# manual_stm_4.net
KiCad netlist of a schematic drawn in EAGLE
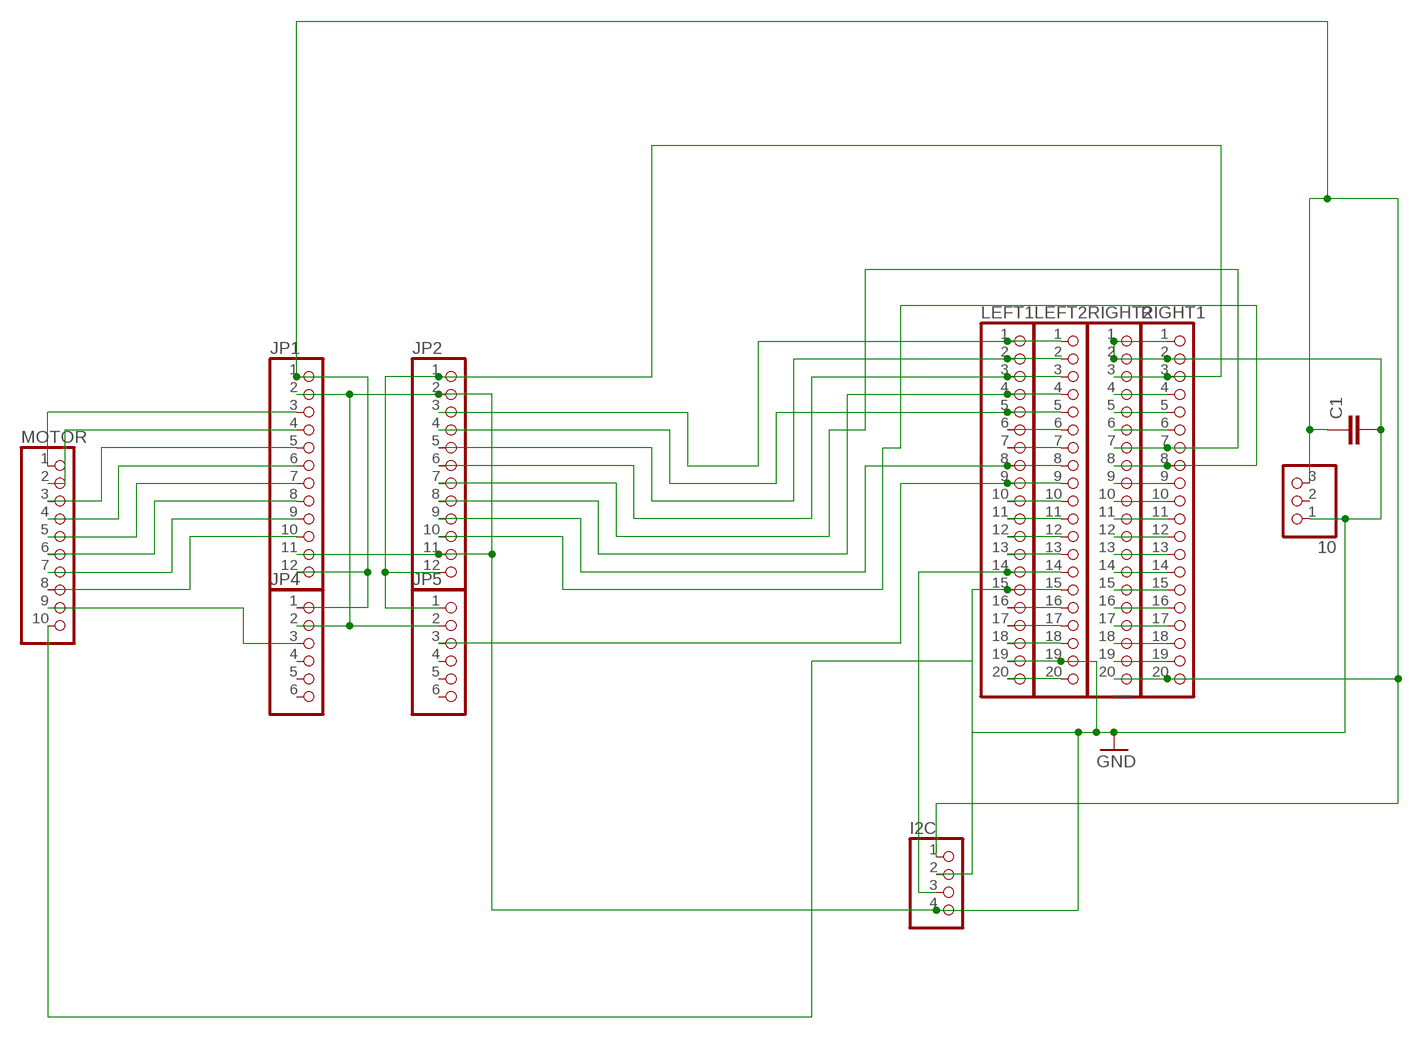
[diagram p0: schematic, sheet 1]

(export (version "E")
  (design (tool "Eeschema 10.0.6"))
  (components
    (comp (ref "10")
      (value "PINHD-1X3")
      (footprint "eagle-import:1X03")
      (libsource (lib "eagle-import") (part "PINHD-1X3"))
    )
    (comp (ref "C1")
      (value "C-EU075-032X103")
      (footprint "eagle-import:C075-032X103")
      (libsource (lib "eagle-import") (part "C-EU075-032X103"))
    )
    (comp (ref "I2C")
      (value "PINHD-1X4")
      (footprint "eagle-import:1X04")
      (libsource (lib "eagle-import") (part "PINHD-1X4"))
    )
    (comp (ref "JP1")
      (value "PINHD-1X12")
      (footprint "eagle-import:1X12")
      (libsource (lib "eagle-import") (part "PINHD-1X12"))
    )
    (comp (ref "JP2")
      (value "PINHD-1X12")
      (footprint "eagle-import:1X12")
      (libsource (lib "eagle-import") (part "PINHD-1X12"))
    )
    (comp (ref "JP4")
      (value "PINHD-1X6")
      (footprint "eagle-import:1X06")
      (libsource (lib "eagle-import") (part "PINHD-1X6"))
    )
    (comp (ref "JP5")
      (value "PINHD-1X6")
      (footprint "eagle-import:1X06")
      (libsource (lib "eagle-import") (part "PINHD-1X6"))
    )
    (comp (ref "LEFT1")
      (value "PINHD-1X20")
      (footprint "eagle-import:1X20")
      (libsource (lib "eagle-import") (part "PINHD-1X20"))
    )
    (comp (ref "LEFT2")
      (value "PINHD-1X20")
      (footprint "eagle-import:1X20")
      (libsource (lib "eagle-import") (part "PINHD-1X20"))
    )
    (comp (ref "MOTOR")
      (value "PINHD-1X10")
      (footprint "eagle-import:1X10")
      (libsource (lib "eagle-import") (part "PINHD-1X10"))
    )
    (comp (ref "RIGHT1")
      (value "PINHD-1X20")
      (footprint "eagle-import:1X20")
      (libsource (lib "eagle-import") (part "PINHD-1X20"))
    )
    (comp (ref "RIGHT2")
      (value "PINHD-1X20")
      (footprint "eagle-import:1X20")
      (libsource (lib "eagle-import") (part "PINHD-1X20"))
    )
  )
  (nets
    (net (code "1") (name "GND") (class "Default")
      (node (ref "10") (pin "1") (pinfunction "1_1") (pintype "passive"))
      (node (ref "C1") (pin "2") (pinfunction "2_2") (pintype "passive"))
      (node (ref "I2C") (pin "4") (pinfunction "4_4") (pintype "passive"))
      (node (ref "JP1") (pin "11") (pinfunction "11_11") (pintype "passive"))
      (node (ref "JP1") (pin "2") (pinfunction "2_2") (pintype "passive"))
      (node (ref "JP2") (pin "11") (pinfunction "11_11") (pintype "passive"))
      (node (ref "JP2") (pin "2") (pinfunction "2_2") (pintype "passive"))
      (node (ref "JP4") (pin "2") (pinfunction "2_2") (pintype "passive"))
      (node (ref "JP5") (pin "2") (pinfunction "2_2") (pintype "passive"))
      (node (ref "LEFT1") (pin "19") (pinfunction "19_19") (pintype "passive"))
      (node (ref "LEFT2") (pin "19") (pinfunction "19_19") (pintype "passive"))
      (node (ref "MOTOR") (pin "10") (pinfunction "10_10") (pintype "passive"))
      (node (ref "RIGHT1") (pin "1") (pinfunction "1_1") (pintype "passive"))
      (node (ref "RIGHT1") (pin "2") (pinfunction "2_2") (pintype "passive"))
      (node (ref "RIGHT2") (pin "1") (pinfunction "1_1") (pintype "passive"))
      (node (ref "RIGHT2") (pin "2") (pinfunction "2_2") (pintype "passive"))
    )
    (net (code "2") (name "Net-(10-Pad3)") (class "Default")
      (node (ref "10") (pin "3") (pinfunction "3_3") (pintype "passive"))
      (node (ref "C1") (pin "1") (pinfunction "1_1") (pintype "passive"))
      (node (ref "I2C") (pin "1") (pinfunction "1_1") (pintype "passive"))
      (node (ref "JP1") (pin "1") (pinfunction "1_1") (pintype "passive"))
      (node (ref "JP1") (pin "12") (pinfunction "12_12") (pintype "passive"))
      (node (ref "JP4") (pin "1") (pinfunction "1_1") (pintype "passive"))
      (node (ref "RIGHT1") (pin "20") (pinfunction "20_20") (pintype "passive"))
      (node (ref "RIGHT2") (pin "20") (pinfunction "20_20") (pintype "passive"))
    )
    (net (code "3") (name "Net-(I2C-Pad2)") (class "Default")
      (node (ref "I2C") (pin "2") (pinfunction "2_2") (pintype "passive"))
      (node (ref "LEFT1") (pin "15") (pinfunction "15_15") (pintype "passive"))
      (node (ref "LEFT2") (pin "15") (pinfunction "15_15") (pintype "passive"))
    )
    (net (code "4") (name "Net-(I2C-Pad3)") (class "Default")
      (node (ref "I2C") (pin "3") (pinfunction "3_3") (pintype "passive"))
      (node (ref "LEFT1") (pin "14") (pinfunction "14_14") (pintype "passive"))
      (node (ref "LEFT2") (pin "14") (pinfunction "14_14") (pintype "passive"))
    )
    (net (code "5") (name "Net-(JP1-Pad3)") (class "Default")
      (node (ref "JP1") (pin "3") (pinfunction "3_3") (pintype "passive"))
      (node (ref "MOTOR") (pin "1") (pinfunction "1_1") (pintype "passive"))
    )
    (net (code "6") (name "Net-(JP1-Pad4)") (class "Default")
      (node (ref "JP1") (pin "4") (pinfunction "4_4") (pintype "passive"))
      (node (ref "MOTOR") (pin "2") (pinfunction "2_2") (pintype "passive"))
    )
    (net (code "7") (name "Net-(JP1-Pad5)") (class "Default")
      (node (ref "JP1") (pin "5") (pinfunction "5_5") (pintype "passive"))
      (node (ref "MOTOR") (pin "3") (pinfunction "3_3") (pintype "passive"))
    )
    (net (code "8") (name "Net-(JP1-Pad6)") (class "Default")
      (node (ref "JP1") (pin "6") (pinfunction "6_6") (pintype "passive"))
      (node (ref "MOTOR") (pin "4") (pinfunction "4_4") (pintype "passive"))
    )
    (net (code "9") (name "Net-(JP1-Pad7)") (class "Default")
      (node (ref "JP1") (pin "7") (pinfunction "7_7") (pintype "passive"))
      (node (ref "MOTOR") (pin "5") (pinfunction "5_5") (pintype "passive"))
    )
    (net (code "10") (name "Net-(JP1-Pad8)") (class "Default")
      (node (ref "JP1") (pin "8") (pinfunction "8_8") (pintype "passive"))
      (node (ref "MOTOR") (pin "6") (pinfunction "6_6") (pintype "passive"))
    )
    (net (code "11") (name "Net-(JP1-Pad9)") (class "Default")
      (node (ref "JP1") (pin "9") (pinfunction "9_9") (pintype "passive"))
      (node (ref "MOTOR") (pin "7") (pinfunction "7_7") (pintype "passive"))
    )
    (net (code "12") (name "Net-(JP1-Pad10)") (class "Default")
      (node (ref "JP1") (pin "10") (pinfunction "10_10") (pintype "passive"))
      (node (ref "MOTOR") (pin "8") (pinfunction "8_8") (pintype "passive"))
    )
    (net (code "13") (name "Net-(JP2-Pad1)") (class "Default")
      (node (ref "JP2") (pin "1") (pinfunction "1_1") (pintype "passive"))
      (node (ref "JP2") (pin "12") (pinfunction "12_12") (pintype "passive"))
      (node (ref "JP5") (pin "1") (pinfunction "1_1") (pintype "passive"))
      (node (ref "RIGHT1") (pin "3") (pinfunction "3_3") (pintype "passive"))
      (node (ref "RIGHT2") (pin "3") (pinfunction "3_3") (pintype "passive"))
    )
    (net (code "14") (name "Net-(JP2-Pad3)") (class "Default")
      (node (ref "JP2") (pin "3") (pinfunction "3_3") (pintype "passive"))
      (node (ref "LEFT1") (pin "1") (pinfunction "1_1") (pintype "passive"))
      (node (ref "LEFT2") (pin "1") (pinfunction "1_1") (pintype "passive"))
    )
    (net (code "15") (name "Net-(JP2-Pad4)") (class "Default")
      (node (ref "JP2") (pin "4") (pinfunction "4_4") (pintype "passive"))
      (node (ref "LEFT1") (pin "5") (pinfunction "5_5") (pintype "passive"))
      (node (ref "LEFT2") (pin "5") (pinfunction "5_5") (pintype "passive"))
    )
    (net (code "16") (name "Net-(JP2-Pad5)") (class "Default")
      (node (ref "JP2") (pin "5") (pinfunction "5_5") (pintype "passive"))
      (node (ref "LEFT1") (pin "2") (pinfunction "2_2") (pintype "passive"))
      (node (ref "LEFT2") (pin "2") (pinfunction "2_2") (pintype "passive"))
    )
    (net (code "17") (name "Net-(JP2-Pad6)") (class "Default")
      (node (ref "JP2") (pin "6") (pinfunction "6_6") (pintype "passive"))
      (node (ref "LEFT1") (pin "3") (pinfunction "3_3") (pintype "passive"))
      (node (ref "LEFT2") (pin "3") (pinfunction "3_3") (pintype "passive"))
    )
    (net (code "18") (name "Net-(JP2-Pad7)") (class "Default")
      (node (ref "JP2") (pin "7") (pinfunction "7_7") (pintype "passive"))
      (node (ref "RIGHT1") (pin "7") (pinfunction "7_7") (pintype "passive"))
      (node (ref "RIGHT2") (pin "7") (pinfunction "7_7") (pintype "passive"))
    )
    (net (code "19") (name "Net-(JP2-Pad8)") (class "Default")
      (node (ref "JP2") (pin "8") (pinfunction "8_8") (pintype "passive"))
      (node (ref "LEFT1") (pin "4") (pinfunction "4_4") (pintype "passive"))
      (node (ref "LEFT2") (pin "4") (pinfunction "4_4") (pintype "passive"))
    )
    (net (code "20") (name "Net-(JP2-Pad9)") (class "Default")
      (node (ref "JP2") (pin "9") (pinfunction "9_9") (pintype "passive"))
      (node (ref "LEFT1") (pin "8") (pinfunction "8_8") (pintype "passive"))
      (node (ref "LEFT2") (pin "8") (pinfunction "8_8") (pintype "passive"))
    )
    (net (code "21") (name "Net-(JP2-Pad10)") (class "Default")
      (node (ref "JP2") (pin "10") (pinfunction "10_10") (pintype "passive"))
      (node (ref "RIGHT1") (pin "8") (pinfunction "8_8") (pintype "passive"))
      (node (ref "RIGHT2") (pin "8") (pinfunction "8_8") (pintype "passive"))
    )
    (net (code "22") (name "Net-(JP4-Pad3)") (class "Default")
      (node (ref "JP4") (pin "3") (pinfunction "3_3") (pintype "passive"))
      (node (ref "MOTOR") (pin "9") (pinfunction "9_9") (pintype "passive"))
    )
    (net (code "23") (name "Net-(JP5-Pad3)") (class "Default")
      (node (ref "JP5") (pin "3") (pinfunction "3_3") (pintype "passive"))
      (node (ref "LEFT1") (pin "9") (pinfunction "9_9") (pintype "passive"))
      (node (ref "LEFT2") (pin "9") (pinfunction "9_9") (pintype "passive"))
    )
    (net (code "24") (name "Net-(LEFT1-Pad6)") (class "Default")
      (node (ref "LEFT1") (pin "6") (pinfunction "6_6") (pintype "passive"))
      (node (ref "LEFT2") (pin "6") (pinfunction "6_6") (pintype "passive"))
    )
    (net (code "25") (name "Net-(LEFT1-Pad7)") (class "Default")
      (node (ref "LEFT1") (pin "7") (pinfunction "7_7") (pintype "passive"))
      (node (ref "LEFT2") (pin "7") (pinfunction "7_7") (pintype "passive"))
    )
    (net (code "26") (name "Net-(LEFT1-Pad10)") (class "Default")
      (node (ref "LEFT1") (pin "10") (pinfunction "10_10") (pintype "passive"))
      (node (ref "LEFT2") (pin "10") (pinfunction "10_10") (pintype "passive"))
    )
    (net (code "27") (name "Net-(LEFT1-Pad11)") (class "Default")
      (node (ref "LEFT1") (pin "11") (pinfunction "11_11") (pintype "passive"))
      (node (ref "LEFT2") (pin "11") (pinfunction "11_11") (pintype "passive"))
    )
    (net (code "28") (name "Net-(LEFT1-Pad12)") (class "Default")
      (node (ref "LEFT1") (pin "12") (pinfunction "12_12") (pintype "passive"))
      (node (ref "LEFT2") (pin "12") (pinfunction "12_12") (pintype "passive"))
    )
    (net (code "29") (name "Net-(LEFT1-Pad13)") (class "Default")
      (node (ref "LEFT1") (pin "13") (pinfunction "13_13") (pintype "passive"))
      (node (ref "LEFT2") (pin "13") (pinfunction "13_13") (pintype "passive"))
    )
    (net (code "30") (name "Net-(LEFT1-Pad16)") (class "Default")
      (node (ref "LEFT1") (pin "16") (pinfunction "16_16") (pintype "passive"))
      (node (ref "LEFT2") (pin "16") (pinfunction "16_16") (pintype "passive"))
    )
    (net (code "31") (name "Net-(LEFT1-Pad17)") (class "Default")
      (node (ref "LEFT1") (pin "17") (pinfunction "17_17") (pintype "passive"))
      (node (ref "LEFT2") (pin "17") (pinfunction "17_17") (pintype "passive"))
    )
    (net (code "32") (name "Net-(LEFT1-Pad18)") (class "Default")
      (node (ref "LEFT1") (pin "18") (pinfunction "18_18") (pintype "passive"))
      (node (ref "LEFT2") (pin "18") (pinfunction "18_18") (pintype "passive"))
    )
    (net (code "33") (name "Net-(LEFT1-Pad20)") (class "Default")
      (node (ref "LEFT1") (pin "20") (pinfunction "20_20") (pintype "passive"))
      (node (ref "LEFT2") (pin "20") (pinfunction "20_20") (pintype "passive"))
    )
    (net (code "34") (name "Net-(RIGHT1-Pad4)") (class "Default")
      (node (ref "RIGHT1") (pin "4") (pinfunction "4_4") (pintype "passive"))
      (node (ref "RIGHT2") (pin "4") (pinfunction "4_4") (pintype "passive"))
    )
    (net (code "35") (name "Net-(RIGHT1-Pad5)") (class "Default")
      (node (ref "RIGHT1") (pin "5") (pinfunction "5_5") (pintype "passive"))
      (node (ref "RIGHT2") (pin "5") (pinfunction "5_5") (pintype "passive"))
    )
    (net (code "36") (name "Net-(RIGHT1-Pad6)") (class "Default")
      (node (ref "RIGHT1") (pin "6") (pinfunction "6_6") (pintype "passive"))
      (node (ref "RIGHT2") (pin "6") (pinfunction "6_6") (pintype "passive"))
    )
    (net (code "37") (name "Net-(RIGHT1-Pad9)") (class "Default")
      (node (ref "RIGHT1") (pin "9") (pinfunction "9_9") (pintype "passive"))
      (node (ref "RIGHT2") (pin "9") (pinfunction "9_9") (pintype "passive"))
    )
    (net (code "38") (name "Net-(RIGHT1-Pad10)") (class "Default")
      (node (ref "RIGHT1") (pin "10") (pinfunction "10_10") (pintype "passive"))
      (node (ref "RIGHT2") (pin "10") (pinfunction "10_10") (pintype "passive"))
    )
    (net (code "39") (name "Net-(RIGHT1-Pad11)") (class "Default")
      (node (ref "RIGHT1") (pin "11") (pinfunction "11_11") (pintype "passive"))
      (node (ref "RIGHT2") (pin "11") (pinfunction "11_11") (pintype "passive"))
    )
    (net (code "40") (name "Net-(RIGHT1-Pad12)") (class "Default")
      (node (ref "RIGHT1") (pin "12") (pinfunction "12_12") (pintype "passive"))
      (node (ref "RIGHT2") (pin "12") (pinfunction "12_12") (pintype "passive"))
    )
    (net (code "41") (name "Net-(RIGHT1-Pad13)") (class "Default")
      (node (ref "RIGHT1") (pin "13") (pinfunction "13_13") (pintype "passive"))
      (node (ref "RIGHT2") (pin "13") (pinfunction "13_13") (pintype "passive"))
    )
    (net (code "42") (name "Net-(RIGHT1-Pad14)") (class "Default")
      (node (ref "RIGHT1") (pin "14") (pinfunction "14_14") (pintype "passive"))
      (node (ref "RIGHT2") (pin "14") (pinfunction "14_14") (pintype "passive"))
    )
    (net (code "43") (name "Net-(RIGHT1-Pad15)") (class "Default")
      (node (ref "RIGHT1") (pin "15") (pinfunction "15_15") (pintype "passive"))
      (node (ref "RIGHT2") (pin "15") (pinfunction "15_15") (pintype "passive"))
    )
    (net (code "44") (name "Net-(RIGHT1-Pad16)") (class "Default")
      (node (ref "RIGHT1") (pin "16") (pinfunction "16_16") (pintype "passive"))
      (node (ref "RIGHT2") (pin "16") (pinfunction "16_16") (pintype "passive"))
    )
    (net (code "45") (name "Net-(RIGHT1-Pad17)") (class "Default")
      (node (ref "RIGHT1") (pin "17") (pinfunction "17_17") (pintype "passive"))
      (node (ref "RIGHT2") (pin "17") (pinfunction "17_17") (pintype "passive"))
    )
    (net (code "46") (name "Net-(RIGHT1-Pad18)") (class "Default")
      (node (ref "RIGHT1") (pin "18") (pinfunction "18_18") (pintype "passive"))
      (node (ref "RIGHT2") (pin "18") (pinfunction "18_18") (pintype "passive"))
    )
    (net (code "47") (name "Net-(RIGHT1-Pad19)") (class "Default")
      (node (ref "RIGHT1") (pin "19") (pinfunction "19_19") (pintype "passive"))
      (node (ref "RIGHT2") (pin "19") (pinfunction "19_19") (pintype "passive"))
    )
    (net (code "48") (name "unconnected-(10-Pad2)") (class "Default")
      (node (ref "10") (pin "2") (pinfunction "2_2") (pintype "passive"))
    )
    (net (code "49") (name "unconnected-(JP4-Pad4)") (class "Default")
      (node (ref "JP4") (pin "4") (pinfunction "4_4") (pintype "passive"))
    )
    (net (code "50") (name "unconnected-(JP4-Pad5)") (class "Default")
      (node (ref "JP4") (pin "5") (pinfunction "5_5") (pintype "passive"))
    )
    (net (code "51") (name "unconnected-(JP4-Pad6)") (class "Default")
      (node (ref "JP4") (pin "6") (pinfunction "6_6") (pintype "passive"))
    )
    (net (code "52") (name "unconnected-(JP5-Pad4)") (class "Default")
      (node (ref "JP5") (pin "4") (pinfunction "4_4") (pintype "passive"))
    )
    (net (code "53") (name "unconnected-(JP5-Pad5)") (class "Default")
      (node (ref "JP5") (pin "5") (pinfunction "5_5") (pintype "passive"))
    )
    (net (code "54") (name "unconnected-(JP5-Pad6)") (class "Default")
      (node (ref "JP5") (pin "6") (pinfunction "6_6") (pintype "passive"))
    )
  )
)
